# high_side_driver_fix.net
KiCad netlist of a schematic drawn in EAGLE
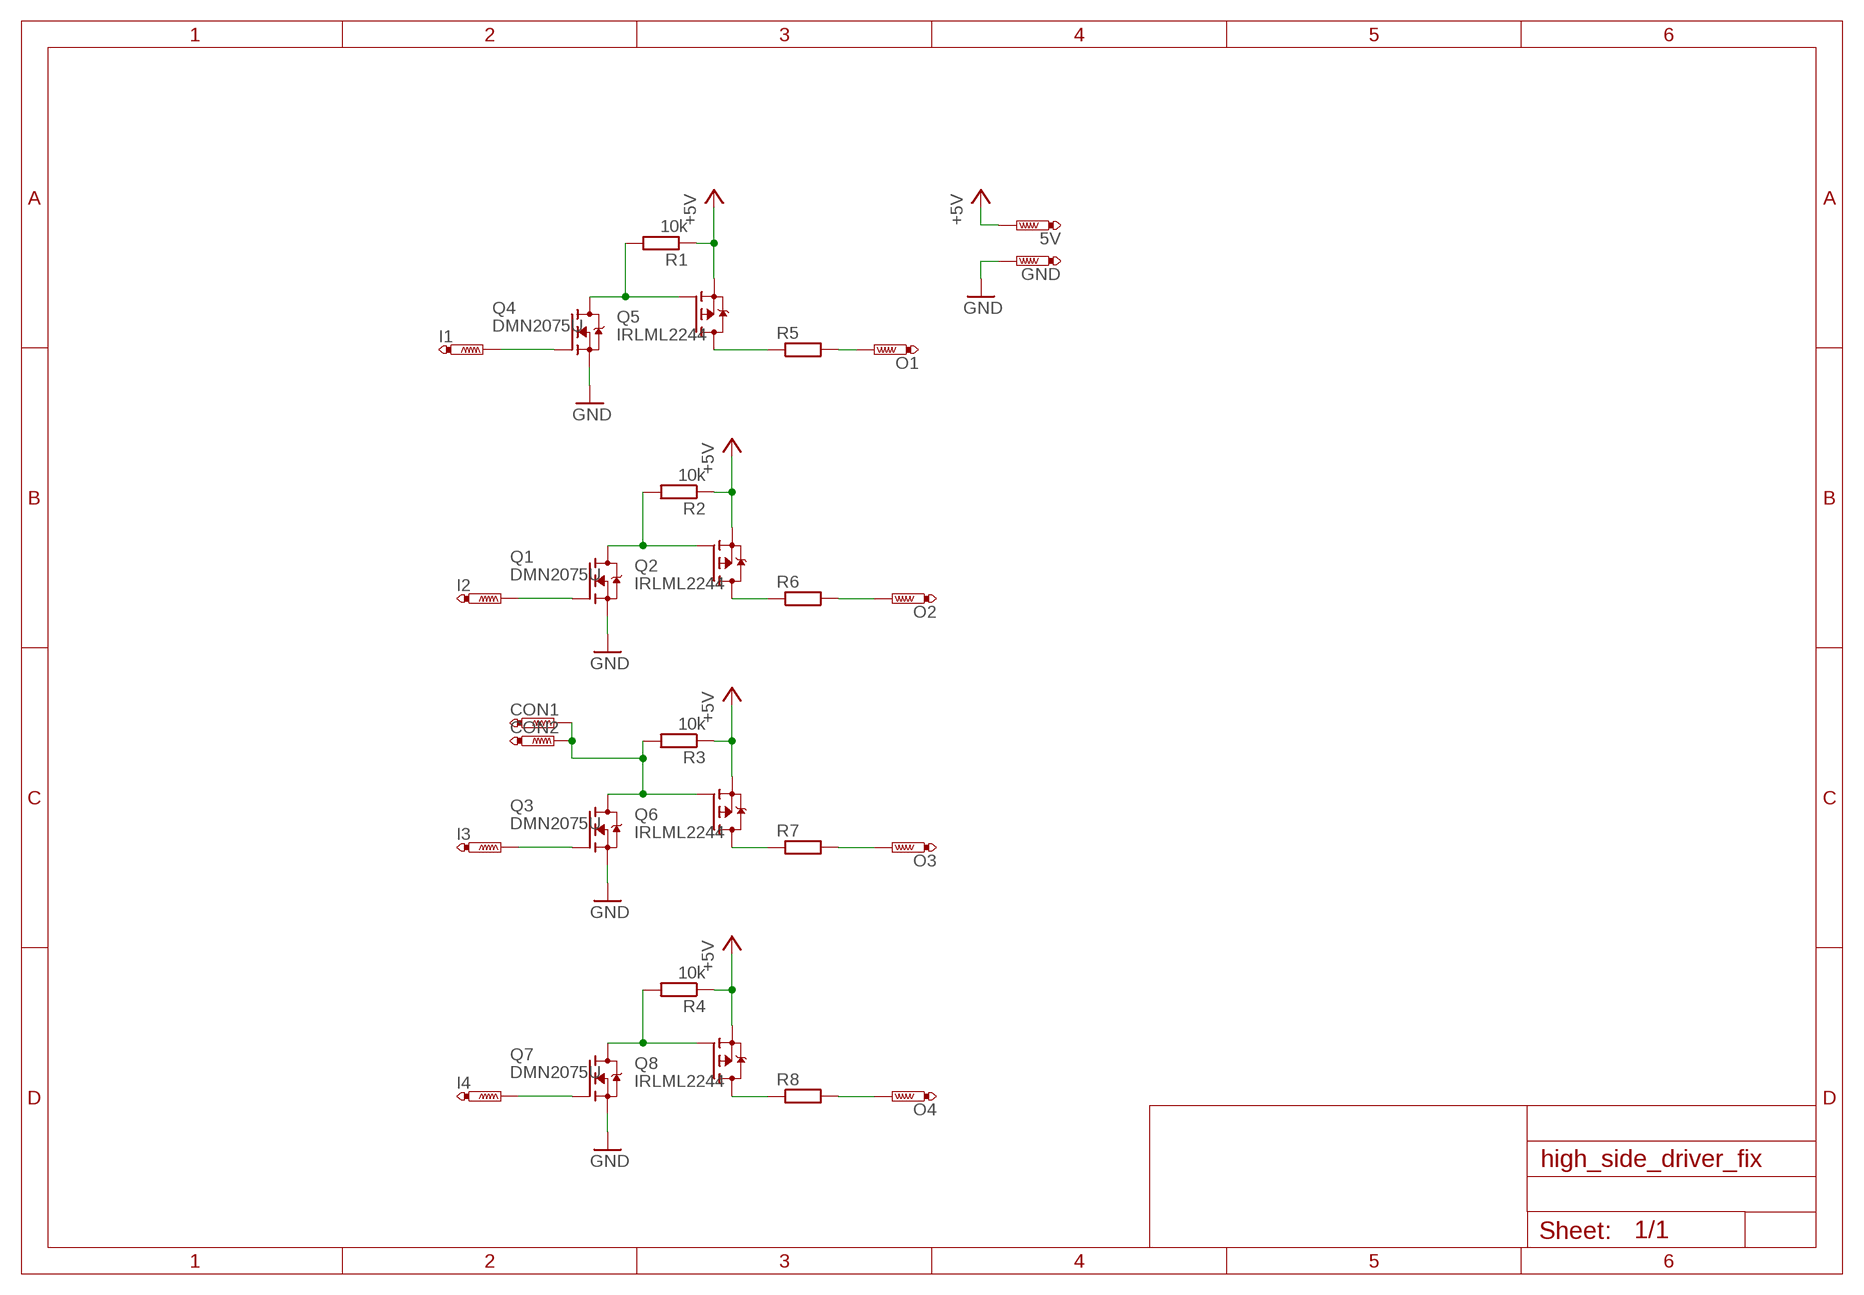
[diagram p0: schematic, sheet 1]

(export (version "E")
  (design (tool "Eeschema 10.0.6"))
  (components
    (comp (ref "5V")
      (value "PTR1TP11SQ")
      (footprint "eagle-import:TP11SQ")
      (libsource (lib "eagle-import") (part "PTR1TP11SQ"))
    )
    (comp (ref "CON1")
      (value "PTR1TP08SQ")
      (footprint "eagle-import:TP08SQ")
      (libsource (lib "eagle-import") (part "PTR1TP08SQ"))
    )
    (comp (ref "CON2")
      (value "PTR1TP08SQ")
      (footprint "eagle-import:TP08SQ")
      (libsource (lib "eagle-import") (part "PTR1TP08SQ"))
    )
    (comp (ref "GND")
      (value "PTR1TP11SQ")
      (footprint "eagle-import:TP11SQ")
      (libsource (lib "eagle-import") (part "PTR1TP11SQ"))
    )
    (comp (ref "I1")
      (value "PTR1TP11SQ")
      (footprint "eagle-import:TP11SQ")
      (libsource (lib "eagle-import") (part "PTR1TP11SQ"))
    )
    (comp (ref "I2")
      (value "PTR1TP11SQ")
      (footprint "eagle-import:TP11SQ")
      (libsource (lib "eagle-import") (part "PTR1TP11SQ"))
    )
    (comp (ref "I3")
      (value "PTR1TP11SQ")
      (footprint "eagle-import:TP11SQ")
      (libsource (lib "eagle-import") (part "PTR1TP11SQ"))
    )
    (comp (ref "I4")
      (value "PTR1TP11SQ")
      (footprint "eagle-import:TP11SQ")
      (libsource (lib "eagle-import") (part "PTR1TP11SQ"))
    )
    (comp (ref "O1")
      (value "PTR1TP11SQ")
      (footprint "eagle-import:TP11SQ")
      (libsource (lib "eagle-import") (part "PTR1TP11SQ"))
    )
    (comp (ref "O2")
      (value "PTR1TP11SQ")
      (footprint "eagle-import:TP11SQ")
      (libsource (lib "eagle-import") (part "PTR1TP11SQ"))
    )
    (comp (ref "O3")
      (value "PTR1TP11SQ")
      (footprint "eagle-import:TP11SQ")
      (libsource (lib "eagle-import") (part "PTR1TP11SQ"))
    )
    (comp (ref "O4")
      (value "PTR1TP11SQ")
      (footprint "eagle-import:TP11SQ")
      (libsource (lib "eagle-import") (part "PTR1TP11SQ"))
    )
    (comp (ref "Q1")
      (value "DMN2075U")
      (footprint "eagle-import:SOT95P240X112-3N")
      (libsource (lib "eagle-import") (part "DMN2075U"))
    )
    (comp (ref "Q2")
      (value "IRLML2244")
      (footprint "eagle-import:SOT95P240X112-3N")
      (libsource (lib "eagle-import") (part "IRLML2244"))
    )
    (comp (ref "Q3")
      (value "DMN2075U")
      (footprint "eagle-import:SOT95P240X112-3N")
      (libsource (lib "eagle-import") (part "DMN2075U"))
    )
    (comp (ref "Q4")
      (value "DMN2075U")
      (footprint "eagle-import:SOT95P240X112-3N")
      (libsource (lib "eagle-import") (part "DMN2075U"))
    )
    (comp (ref "Q5")
      (value "IRLML2244")
      (footprint "eagle-import:SOT95P240X112-3N")
      (libsource (lib "eagle-import") (part "IRLML2244"))
    )
    (comp (ref "Q6")
      (value "IRLML2244")
      (footprint "eagle-import:SOT95P240X112-3N")
      (libsource (lib "eagle-import") (part "IRLML2244"))
    )
    (comp (ref "Q7")
      (value "DMN2075U")
      (footprint "eagle-import:SOT95P240X112-3N")
      (libsource (lib "eagle-import") (part "DMN2075U"))
    )
    (comp (ref "Q8")
      (value "IRLML2244")
      (footprint "eagle-import:SOT95P240X112-3N")
      (libsource (lib "eagle-import") (part "IRLML2244"))
    )
    (comp (ref "R1")
      (value "10k")
      (footprint "eagle-import:R0603")
      (libsource (lib "eagle-import") (part "R-EU_R0603"))
    )
    (comp (ref "R2")
      (value "10k")
      (footprint "eagle-import:R0603")
      (libsource (lib "eagle-import") (part "R-EU_R0603"))
    )
    (comp (ref "R3")
      (value "10k")
      (footprint "eagle-import:R0603")
      (libsource (lib "eagle-import") (part "R-EU_R0603"))
    )
    (comp (ref "R4")
      (value "10k")
      (footprint "eagle-import:R0603")
      (libsource (lib "eagle-import") (part "R-EU_R0603"))
    )
    (comp (ref "R5")
      (value "R-EU_M0805")
      (footprint "eagle-import:M0805")
      (libsource (lib "eagle-import") (part "R-EU_M0805"))
    )
    (comp (ref "R6")
      (value "R-EU_M0805")
      (footprint "eagle-import:M0805")
      (libsource (lib "eagle-import") (part "R-EU_M0805"))
    )
    (comp (ref "R7")
      (value "R-EU_M0805")
      (footprint "eagle-import:M0805")
      (libsource (lib "eagle-import") (part "R-EU_M0805"))
    )
    (comp (ref "R8")
      (value "R-EU_M0805")
      (footprint "eagle-import:M0805")
      (libsource (lib "eagle-import") (part "R-EU_M0805"))
    )
  )
  (nets
    (net (code "1") (name "+5V") (class "Default")
      (node (ref "5V") (pin "TP") (pinfunction "TP_TP") (pintype "input"))
      (node (ref "Q2") (pin "S") (pinfunction "S_S") (pintype "passive"))
      (node (ref "Q5") (pin "S") (pinfunction "S_S") (pintype "passive"))
      (node (ref "Q6") (pin "S") (pinfunction "S_S") (pintype "passive"))
      (node (ref "Q8") (pin "S") (pinfunction "S_S") (pintype "passive"))
      (node (ref "R1") (pin "1") (pinfunction "1_1") (pintype "passive"))
      (node (ref "R2") (pin "1") (pinfunction "1_1") (pintype "passive"))
      (node (ref "R3") (pin "1") (pinfunction "1_1") (pintype "passive"))
      (node (ref "R4") (pin "1") (pinfunction "1_1") (pintype "passive"))
    )
    (net (code "2") (name "GND") (class "Default")
      (node (ref "GND") (pin "TP") (pinfunction "TP_TP") (pintype "input"))
      (node (ref "Q1") (pin "S") (pinfunction "S_S") (pintype "passive"))
      (node (ref "Q3") (pin "S") (pinfunction "S_S") (pintype "passive"))
      (node (ref "Q4") (pin "S") (pinfunction "S_S") (pintype "passive"))
      (node (ref "Q7") (pin "S") (pinfunction "S_S") (pintype "passive"))
    )
    (net (code "3") (name "Net-(CON1-PadTP)") (class "Default")
      (node (ref "CON1") (pin "TP") (pinfunction "TP_TP") (pintype "input"))
      (node (ref "CON2") (pin "TP") (pinfunction "TP_TP") (pintype "input"))
      (node (ref "Q3") (pin "D") (pinfunction "D_D") (pintype "passive"))
      (node (ref "Q6") (pin "G") (pinfunction "G_G") (pintype "passive"))
      (node (ref "R3") (pin "2") (pinfunction "2_2") (pintype "passive"))
    )
    (net (code "4") (name "Net-(I1-PadTP)") (class "Default")
      (node (ref "I1") (pin "TP") (pinfunction "TP_TP") (pintype "input"))
      (node (ref "Q4") (pin "G") (pinfunction "G_G") (pintype "passive"))
    )
    (net (code "5") (name "Net-(I2-PadTP)") (class "Default")
      (node (ref "I2") (pin "TP") (pinfunction "TP_TP") (pintype "input"))
      (node (ref "Q1") (pin "G") (pinfunction "G_G") (pintype "passive"))
    )
    (net (code "6") (name "Net-(I3-PadTP)") (class "Default")
      (node (ref "I3") (pin "TP") (pinfunction "TP_TP") (pintype "input"))
      (node (ref "Q3") (pin "G") (pinfunction "G_G") (pintype "passive"))
    )
    (net (code "7") (name "Net-(I4-PadTP)") (class "Default")
      (node (ref "I4") (pin "TP") (pinfunction "TP_TP") (pintype "input"))
      (node (ref "Q7") (pin "G") (pinfunction "G_G") (pintype "passive"))
    )
    (net (code "8") (name "Net-(O1-PadTP)") (class "Default")
      (node (ref "O1") (pin "TP") (pinfunction "TP_TP") (pintype "input"))
      (node (ref "R5") (pin "2") (pinfunction "2_2") (pintype "passive"))
    )
    (net (code "9") (name "Net-(O2-PadTP)") (class "Default")
      (node (ref "O2") (pin "TP") (pinfunction "TP_TP") (pintype "input"))
      (node (ref "R6") (pin "2") (pinfunction "2_2") (pintype "passive"))
    )
    (net (code "10") (name "Net-(O3-PadTP)") (class "Default")
      (node (ref "O3") (pin "TP") (pinfunction "TP_TP") (pintype "input"))
      (node (ref "R7") (pin "2") (pinfunction "2_2") (pintype "passive"))
    )
    (net (code "11") (name "Net-(O4-PadTP)") (class "Default")
      (node (ref "O4") (pin "TP") (pinfunction "TP_TP") (pintype "input"))
      (node (ref "R8") (pin "2") (pinfunction "2_2") (pintype "passive"))
    )
    (net (code "12") (name "Net-(Q1-PadD)") (class "Default")
      (node (ref "Q1") (pin "D") (pinfunction "D_D") (pintype "passive"))
      (node (ref "Q2") (pin "G") (pinfunction "G_G") (pintype "passive"))
      (node (ref "R2") (pin "2") (pinfunction "2_2") (pintype "passive"))
    )
    (net (code "13") (name "Net-(Q2-PadD)") (class "Default")
      (node (ref "Q2") (pin "D") (pinfunction "D_D") (pintype "passive"))
      (node (ref "R6") (pin "1") (pinfunction "1_1") (pintype "passive"))
    )
    (net (code "14") (name "Net-(Q4-PadD)") (class "Default")
      (node (ref "Q4") (pin "D") (pinfunction "D_D") (pintype "passive"))
      (node (ref "Q5") (pin "G") (pinfunction "G_G") (pintype "passive"))
      (node (ref "R1") (pin "2") (pinfunction "2_2") (pintype "passive"))
    )
    (net (code "15") (name "Net-(Q5-PadD)") (class "Default")
      (node (ref "Q5") (pin "D") (pinfunction "D_D") (pintype "passive"))
      (node (ref "R5") (pin "1") (pinfunction "1_1") (pintype "passive"))
    )
    (net (code "16") (name "Net-(Q6-PadD)") (class "Default")
      (node (ref "Q6") (pin "D") (pinfunction "D_D") (pintype "passive"))
      (node (ref "R7") (pin "1") (pinfunction "1_1") (pintype "passive"))
    )
    (net (code "17") (name "Net-(Q7-PadD)") (class "Default")
      (node (ref "Q7") (pin "D") (pinfunction "D_D") (pintype "passive"))
      (node (ref "Q8") (pin "G") (pinfunction "G_G") (pintype "passive"))
      (node (ref "R4") (pin "2") (pinfunction "2_2") (pintype "passive"))
    )
    (net (code "18") (name "Net-(Q8-PadD)") (class "Default")
      (node (ref "Q8") (pin "D") (pinfunction "D_D") (pintype "passive"))
      (node (ref "R8") (pin "1") (pinfunction "1_1") (pintype "passive"))
    )
  )
)
